# Adafruit_PMSA003I.net
KiCad netlist of a schematic drawn in EAGLE
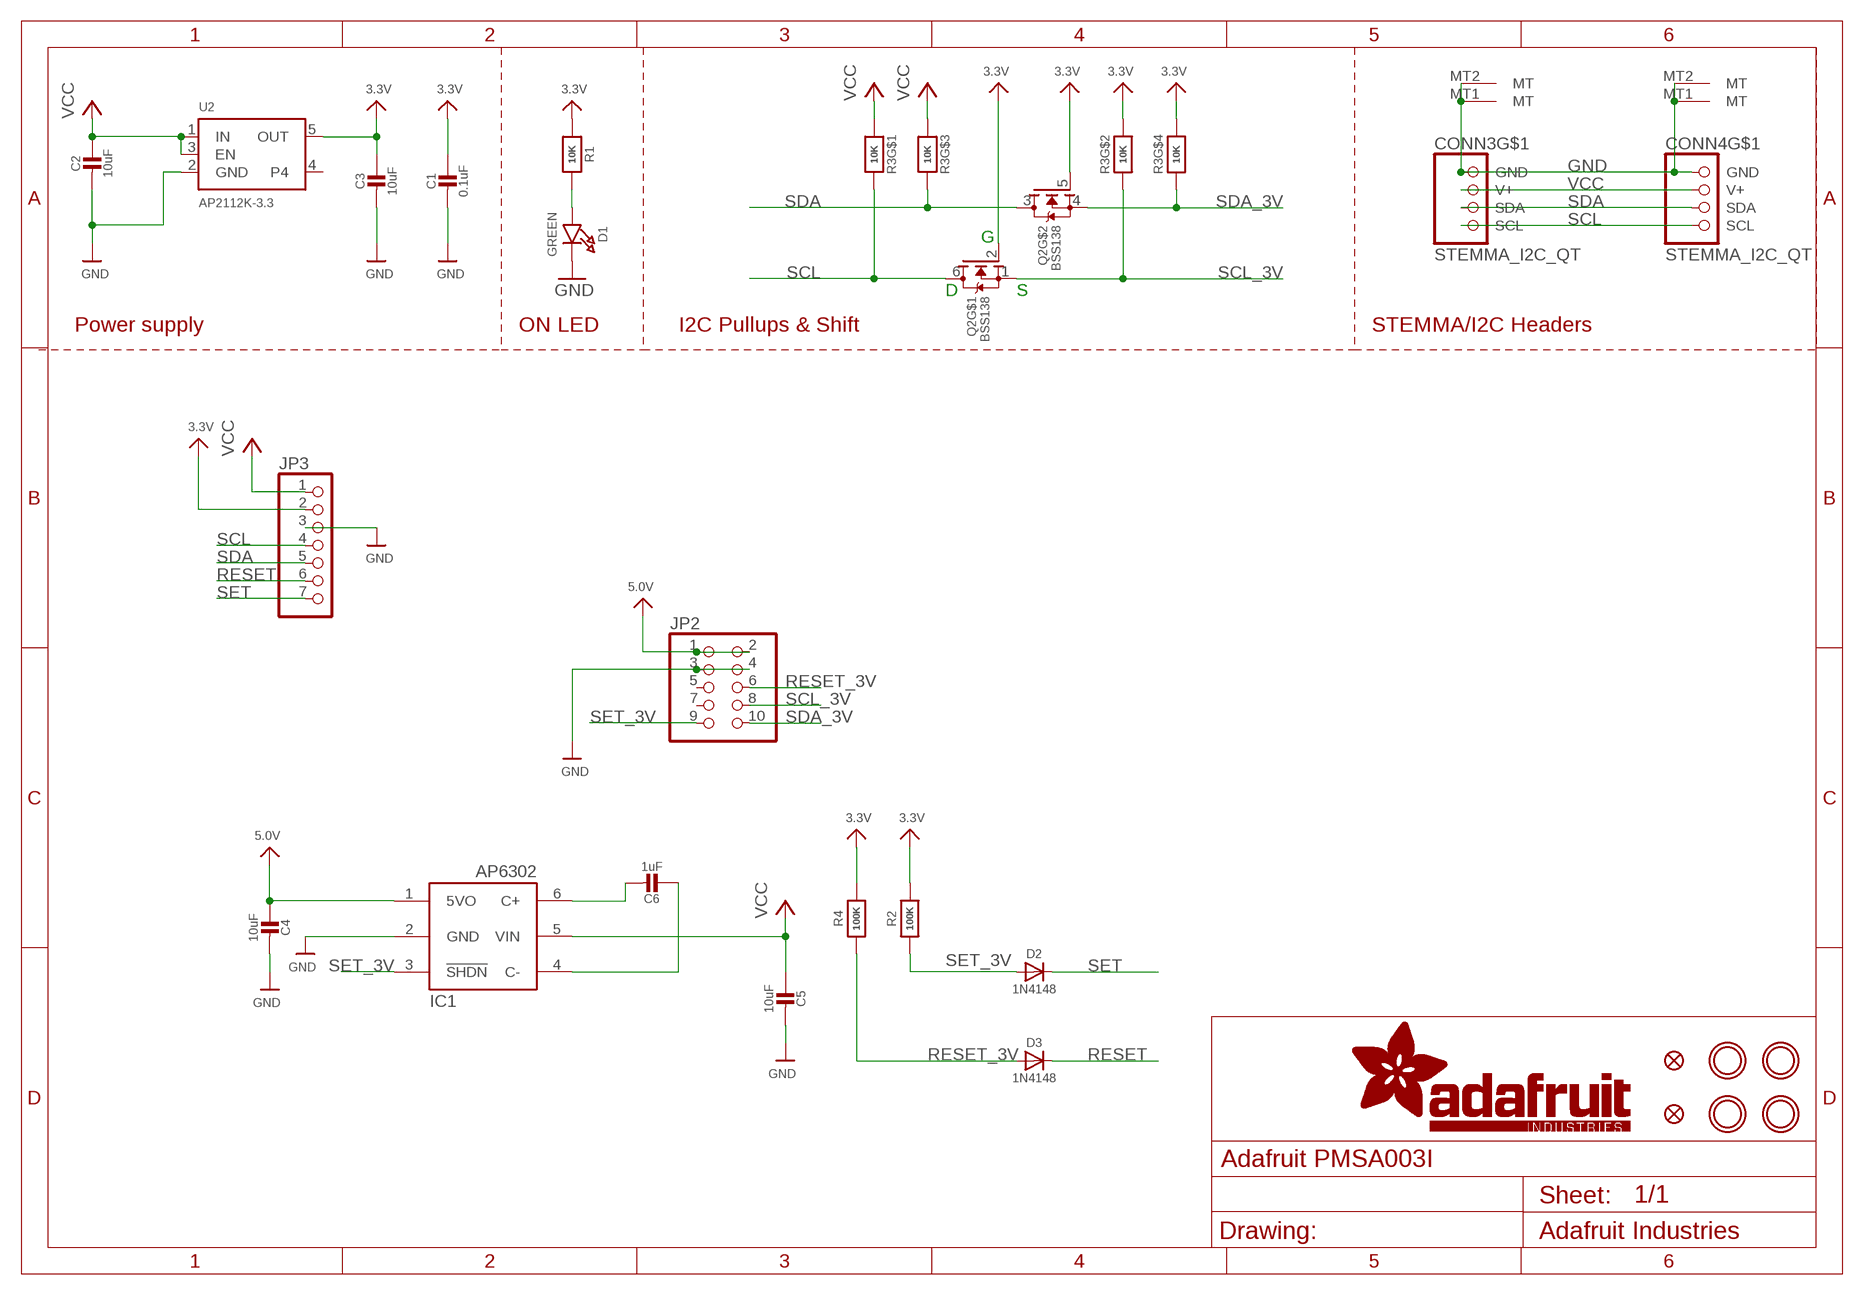
[diagram p0: schematic, sheet 1]

(export (version "E")
  (design (tool "Eeschema 10.0.6"))
  (components
    (comp (ref "C1")
      (value "0.1uF")
      (footprint "eagle-import:0603-NO")
      (libsource (lib "eagle-import") (part "CAP_CERAMIC0603_NO"))
    )
    (comp (ref "C2")
      (value "10uF")
      (footprint "eagle-import:0805-NO")
      (libsource (lib "eagle-import") (part "CAP_CERAMIC0805-NOOUTLINE"))
    )
    (comp (ref "C3")
      (value "10uF")
      (footprint "eagle-import:0805-NO")
      (libsource (lib "eagle-import") (part "CAP_CERAMIC0805-NOOUTLINE"))
    )
    (comp (ref "C4")
      (value "10uF")
      (footprint "eagle-import:0805-NO")
      (libsource (lib "eagle-import") (part "CAP_CERAMIC0805-NOOUTLINE"))
    )
    (comp (ref "C5")
      (value "10uF")
      (footprint "eagle-import:0805_10MGAP")
      (libsource (lib "eagle-import") (part "CAP_CERAMIC0805_10MGAP"))
    )
    (comp (ref "C6")
      (value "1uF")
      (footprint "eagle-import:0805-NO")
      (libsource (lib "eagle-import") (part "CAP_CERAMIC0805-NOOUTLINE"))
    )
    (comp (ref "CONN3")
      (value "STEMMA_I2C_QT")
      (footprint "eagle-import:JST_SH4")
      (libsource (lib "eagle-import") (part "STEMMA_I2C_QT"))
    )
    (comp (ref "CONN4")
      (value "STEMMA_I2C_QT")
      (footprint "eagle-import:JST_SH4")
      (libsource (lib "eagle-import") (part "STEMMA_I2C_QT"))
    )
    (comp (ref "D1")
      (value "GREEN")
      (footprint "eagle-import:CHIPLED_0603_NOOUTLINE")
      (libsource (lib "eagle-import") (part "LED0603_NOOUTLINE"))
    )
    (comp (ref "D2")
      (value "1N4148")
      (footprint "eagle-import:SOD-323")
      (libsource (lib "eagle-import") (part "DIODESOD-323"))
    )
    (comp (ref "D3")
      (value "1N4148")
      (footprint "eagle-import:SOD-323")
      (libsource (lib "eagle-import") (part "DIODESOD-323"))
    )
    (comp (ref "FID3")
      (value "FIDUCIAL_1MM")
      (footprint "eagle-import:FIDUCIAL_1MM")
      (libsource (lib "eagle-import") (part "FIDUCIAL_1MM"))
    )
    (comp (ref "FID4")
      (value "FIDUCIAL_1MM")
      (footprint "eagle-import:FIDUCIAL_1MM")
      (libsource (lib "eagle-import") (part "FIDUCIAL_1MM"))
    )
    (comp (ref "IC1")
      (value "AP3602/RT9361")
      (footprint "eagle-import:SOT23-6")
      (libsource (lib "eagle-import") (part "AP3602"))
    )
    (comp (ref "JP2")
      (value "HEADER-2X51.27MM")
      (footprint "eagle-import:2X05_1.27MM_SMT")
      (libsource (lib "eagle-import") (part "HEADER-2X51.27MM"))
    )
    (comp (ref "JP3")
      (value "HEADER-1X770MIL")
      (footprint "eagle-import:1X07_ROUND_70")
      (libsource (lib "eagle-import") (part "HEADER-1X770MIL"))
    )
    (comp (ref "Q2")
      (value "BSS138")
      (footprint "eagle-import:SOT363")
      (libsource (lib "eagle-import") (part "MOSFET-N_DUAL"))
    )
    (comp (ref "R1")
      (value "10K")
      (footprint "eagle-import:0603-NO")
      (libsource (lib "eagle-import") (part "RESISTOR_0603_NOOUT"))
    )
    (comp (ref "R2")
      (value "100K")
      (footprint "eagle-import:0603-NO")
      (libsource (lib "eagle-import") (part "RESISTOR_0603_NOOUT"))
    )
    (comp (ref "R3")
      (value "10K")
      (footprint "eagle-import:RESPACK_4X0603")
      (libsource (lib "eagle-import") (part "RESISTOR_4PACK"))
    )
    (comp (ref "R4")
      (value "100K")
      (footprint "eagle-import:0603-NO")
      (libsource (lib "eagle-import") (part "RESISTOR_0603_NOOUT"))
    )
    (comp (ref "U$1")
      (value "MOUNTINGHOLE2.5")
      (footprint "eagle-import:MOUNTINGHOLE_2.5_PLATED")
      (libsource (lib "eagle-import") (part "MOUNTINGHOLE2.5"))
    )
    (comp (ref "U$17")
      (value "MOUNTINGHOLE2.5")
      (footprint "eagle-import:MOUNTINGHOLE_2.5_PLATED")
      (libsource (lib "eagle-import") (part "MOUNTINGHOLE2.5"))
    )
    (comp (ref "U$19")
      (value "MOUNTINGHOLE2.5")
      (footprint "eagle-import:MOUNTINGHOLE_2.5_PLATED")
      (libsource (lib "eagle-import") (part "MOUNTINGHOLE2.5"))
    )
    (comp (ref "U$21")
      (value "MOUNTINGHOLE2.5")
      (footprint "eagle-import:MOUNTINGHOLE_2.5_PLATED")
      (libsource (lib "eagle-import") (part "MOUNTINGHOLE2.5"))
    )
    (comp (ref "U2")
      (value "AP2112K-3.3")
      (footprint "eagle-import:SOT23-5")
      (libsource (lib "eagle-import") (part "VREG_SOT23-5"))
    )
  )
  (nets
    (net (code "1") (name "/RESET") (class "Default")
      (node (ref "D3") (pin "C") (pinfunction "C_C") (pintype "passive"))
      (node (ref "JP3") (pin "6") (pinfunction "6_6") (pintype "passive"))
    )
    (net (code "2") (name "/RESET_3V") (class "Default")
      (node (ref "D3") (pin "A") (pinfunction "A_A") (pintype "passive"))
      (node (ref "JP2") (pin "6") (pinfunction "6_6") (pintype "passive"))
      (node (ref "R4") (pin "2") (pinfunction "2_2") (pintype "passive"))
    )
    (net (code "3") (name "/SCL") (class "Default")
      (node (ref "CONN3") (pin "4") (pinfunction "SCL_4") (pintype "passive"))
      (node (ref "CONN4") (pin "4") (pinfunction "SCL_4") (pintype "passive"))
      (node (ref "JP3") (pin "4") (pinfunction "4_4") (pintype "passive"))
      (node (ref "Q2") (pin "6") (pinfunction "D_6") (pintype "bidirectional"))
      (node (ref "R3") (pin "8") (pinfunction "2_8") (pintype "passive"))
    )
    (net (code "4") (name "/SCL_3V") (class "Default")
      (node (ref "JP2") (pin "8") (pinfunction "8_8") (pintype "passive"))
      (node (ref "Q2") (pin "1") (pinfunction "S_1") (pintype "bidirectional"))
      (node (ref "R3") (pin "7") (pinfunction "2_7") (pintype "passive"))
    )
    (net (code "5") (name "/SDA") (class "Default")
      (node (ref "CONN3") (pin "3") (pinfunction "SDA_3") (pintype "passive"))
      (node (ref "CONN4") (pin "3") (pinfunction "SDA_3") (pintype "passive"))
      (node (ref "JP3") (pin "5") (pinfunction "5_5") (pintype "passive"))
      (node (ref "Q2") (pin "3") (pinfunction "D_3") (pintype "bidirectional"))
      (node (ref "R3") (pin "6") (pinfunction "2_6") (pintype "passive"))
    )
    (net (code "6") (name "/SDA_3V") (class "Default")
      (node (ref "JP2") (pin "10") (pinfunction "10_10") (pintype "passive"))
      (node (ref "Q2") (pin "4") (pinfunction "S_4") (pintype "bidirectional"))
      (node (ref "R3") (pin "5") (pinfunction "2_5") (pintype "passive"))
    )
    (net (code "7") (name "/SET") (class "Default")
      (node (ref "D2") (pin "C") (pinfunction "C_C") (pintype "passive"))
      (node (ref "JP3") (pin "7") (pinfunction "7_7") (pintype "passive"))
    )
    (net (code "8") (name "/SET_3V") (class "Default")
      (node (ref "D2") (pin "A") (pinfunction "A_A") (pintype "passive"))
      (node (ref "IC1") (pin "3") (pinfunction "~{SHDN}_3") (pintype "input"))
      (node (ref "JP2") (pin "9") (pinfunction "9_9") (pintype "passive"))
      (node (ref "R2") (pin "2") (pinfunction "2_2") (pintype "passive"))
    )
    (net (code "9") (name "3.3V") (class "Default")
      (node (ref "C1") (pin "1") (pinfunction "1_1") (pintype "passive"))
      (node (ref "C3") (pin "1") (pinfunction "1_1") (pintype "passive"))
      (node (ref "JP3") (pin "2") (pinfunction "2_2") (pintype "passive"))
      (node (ref "Q2") (pin "2") (pinfunction "G_2") (pintype "bidirectional"))
      (node (ref "Q2") (pin "5") (pinfunction "G_5") (pintype "bidirectional"))
      (node (ref "R1") (pin "1") (pinfunction "1_1") (pintype "passive"))
      (node (ref "R2") (pin "1") (pinfunction "1_1") (pintype "passive"))
      (node (ref "R3") (pin "2") (pinfunction "1_2") (pintype "passive"))
      (node (ref "R3") (pin "4") (pinfunction "1_4") (pintype "passive"))
      (node (ref "R4") (pin "1") (pinfunction "1_1") (pintype "passive"))
      (node (ref "U2") (pin "5") (pinfunction "OUT_5") (pintype "power_in"))
    )
    (net (code "10") (name "5.0V") (class "Default")
      (node (ref "C4") (pin "1") (pinfunction "1_1") (pintype "passive"))
      (node (ref "IC1") (pin "1") (pinfunction "5VO_1") (pintype "power_in"))
      (node (ref "JP2") (pin "1") (pinfunction "1_1") (pintype "passive"))
      (node (ref "JP2") (pin "2") (pinfunction "2_2") (pintype "passive"))
    )
    (net (code "11") (name "GND") (class "Default")
      (node (ref "C1") (pin "2") (pinfunction "2_2") (pintype "passive"))
      (node (ref "C2") (pin "2") (pinfunction "2_2") (pintype "passive"))
      (node (ref "C3") (pin "2") (pinfunction "2_2") (pintype "passive"))
      (node (ref "C4") (pin "2") (pinfunction "2_2") (pintype "passive"))
      (node (ref "C5") (pin "2") (pinfunction "2_2") (pintype "passive"))
      (node (ref "CONN3") (pin "1") (pinfunction "GND_1") (pintype "passive"))
      (node (ref "CONN3") (pin "MT1") (pinfunction "MT_MT1") (pintype "bidirectional"))
      (node (ref "CONN3") (pin "MT2") (pinfunction "MT_MT2") (pintype "bidirectional"))
      (node (ref "CONN4") (pin "1") (pinfunction "GND_1") (pintype "passive"))
      (node (ref "CONN4") (pin "MT1") (pinfunction "MT_MT1") (pintype "bidirectional"))
      (node (ref "CONN4") (pin "MT2") (pinfunction "MT_MT2") (pintype "bidirectional"))
      (node (ref "D1") (pin "C") (pinfunction "C_C") (pintype "passive"))
      (node (ref "IC1") (pin "2") (pinfunction "GND_2") (pintype "power_in"))
      (node (ref "JP2") (pin "3") (pinfunction "3_3") (pintype "passive"))
      (node (ref "JP2") (pin "4") (pinfunction "4_4") (pintype "passive"))
      (node (ref "JP3") (pin "3") (pinfunction "3_3") (pintype "passive"))
      (node (ref "U2") (pin "2") (pinfunction "GND_2") (pintype "power_in"))
    )
    (net (code "12") (name "Net-(D1-PadA)") (class "Default")
      (node (ref "D1") (pin "A") (pinfunction "A_A") (pintype "passive"))
      (node (ref "R1") (pin "2") (pinfunction "2_2") (pintype "passive"))
    )
    (net (code "13") (name "Net-(IC1-C+)") (class "Default")
      (node (ref "C6") (pin "2") (pinfunction "2_2") (pintype "passive"))
      (node (ref "IC1") (pin "6") (pinfunction "C+_6") (pintype "bidirectional"))
    )
    (net (code "14") (name "Net-(IC1-C-)") (class "Default")
      (node (ref "C6") (pin "1") (pinfunction "1_1") (pintype "passive"))
      (node (ref "IC1") (pin "4") (pinfunction "C-_4") (pintype "bidirectional"))
    )
    (net (code "15") (name "VCC") (class "Default")
      (node (ref "C2") (pin "1") (pinfunction "1_1") (pintype "passive"))
      (node (ref "C5") (pin "1") (pinfunction "1_1") (pintype "passive"))
      (node (ref "CONN3") (pin "2") (pinfunction "V+_2") (pintype "passive"))
      (node (ref "CONN4") (pin "2") (pinfunction "V+_2") (pintype "passive"))
      (node (ref "IC1") (pin "5") (pinfunction "VIN_5") (pintype "power_in"))
      (node (ref "JP3") (pin "1") (pinfunction "1_1") (pintype "passive"))
      (node (ref "R3") (pin "1") (pinfunction "1_1") (pintype "passive"))
      (node (ref "R3") (pin "3") (pinfunction "1_3") (pintype "passive"))
      (node (ref "U2") (pin "1") (pinfunction "IN_1") (pintype "power_in"))
      (node (ref "U2") (pin "3") (pinfunction "EN_3") (pintype "input"))
    )
    (net (code "16") (name "unconnected-(JP2-Pad5)") (class "Default")
      (node (ref "JP2") (pin "5") (pinfunction "5_5") (pintype "passive"))
    )
    (net (code "17") (name "unconnected-(JP2-Pad7)") (class "Default")
      (node (ref "JP2") (pin "7") (pinfunction "7_7") (pintype "passive"))
    )
    (net (code "18") (name "unconnected-(U2-P4-Pad4)") (class "Default")
      (node (ref "U2") (pin "4") (pinfunction "P4_4") (pintype "bidirectional"))
    )
  )
)
